# axiom_beta_plugin_module_1xHDMI_v0_2_6bb.net
KiCad netlist of a schematic drawn in EAGLE
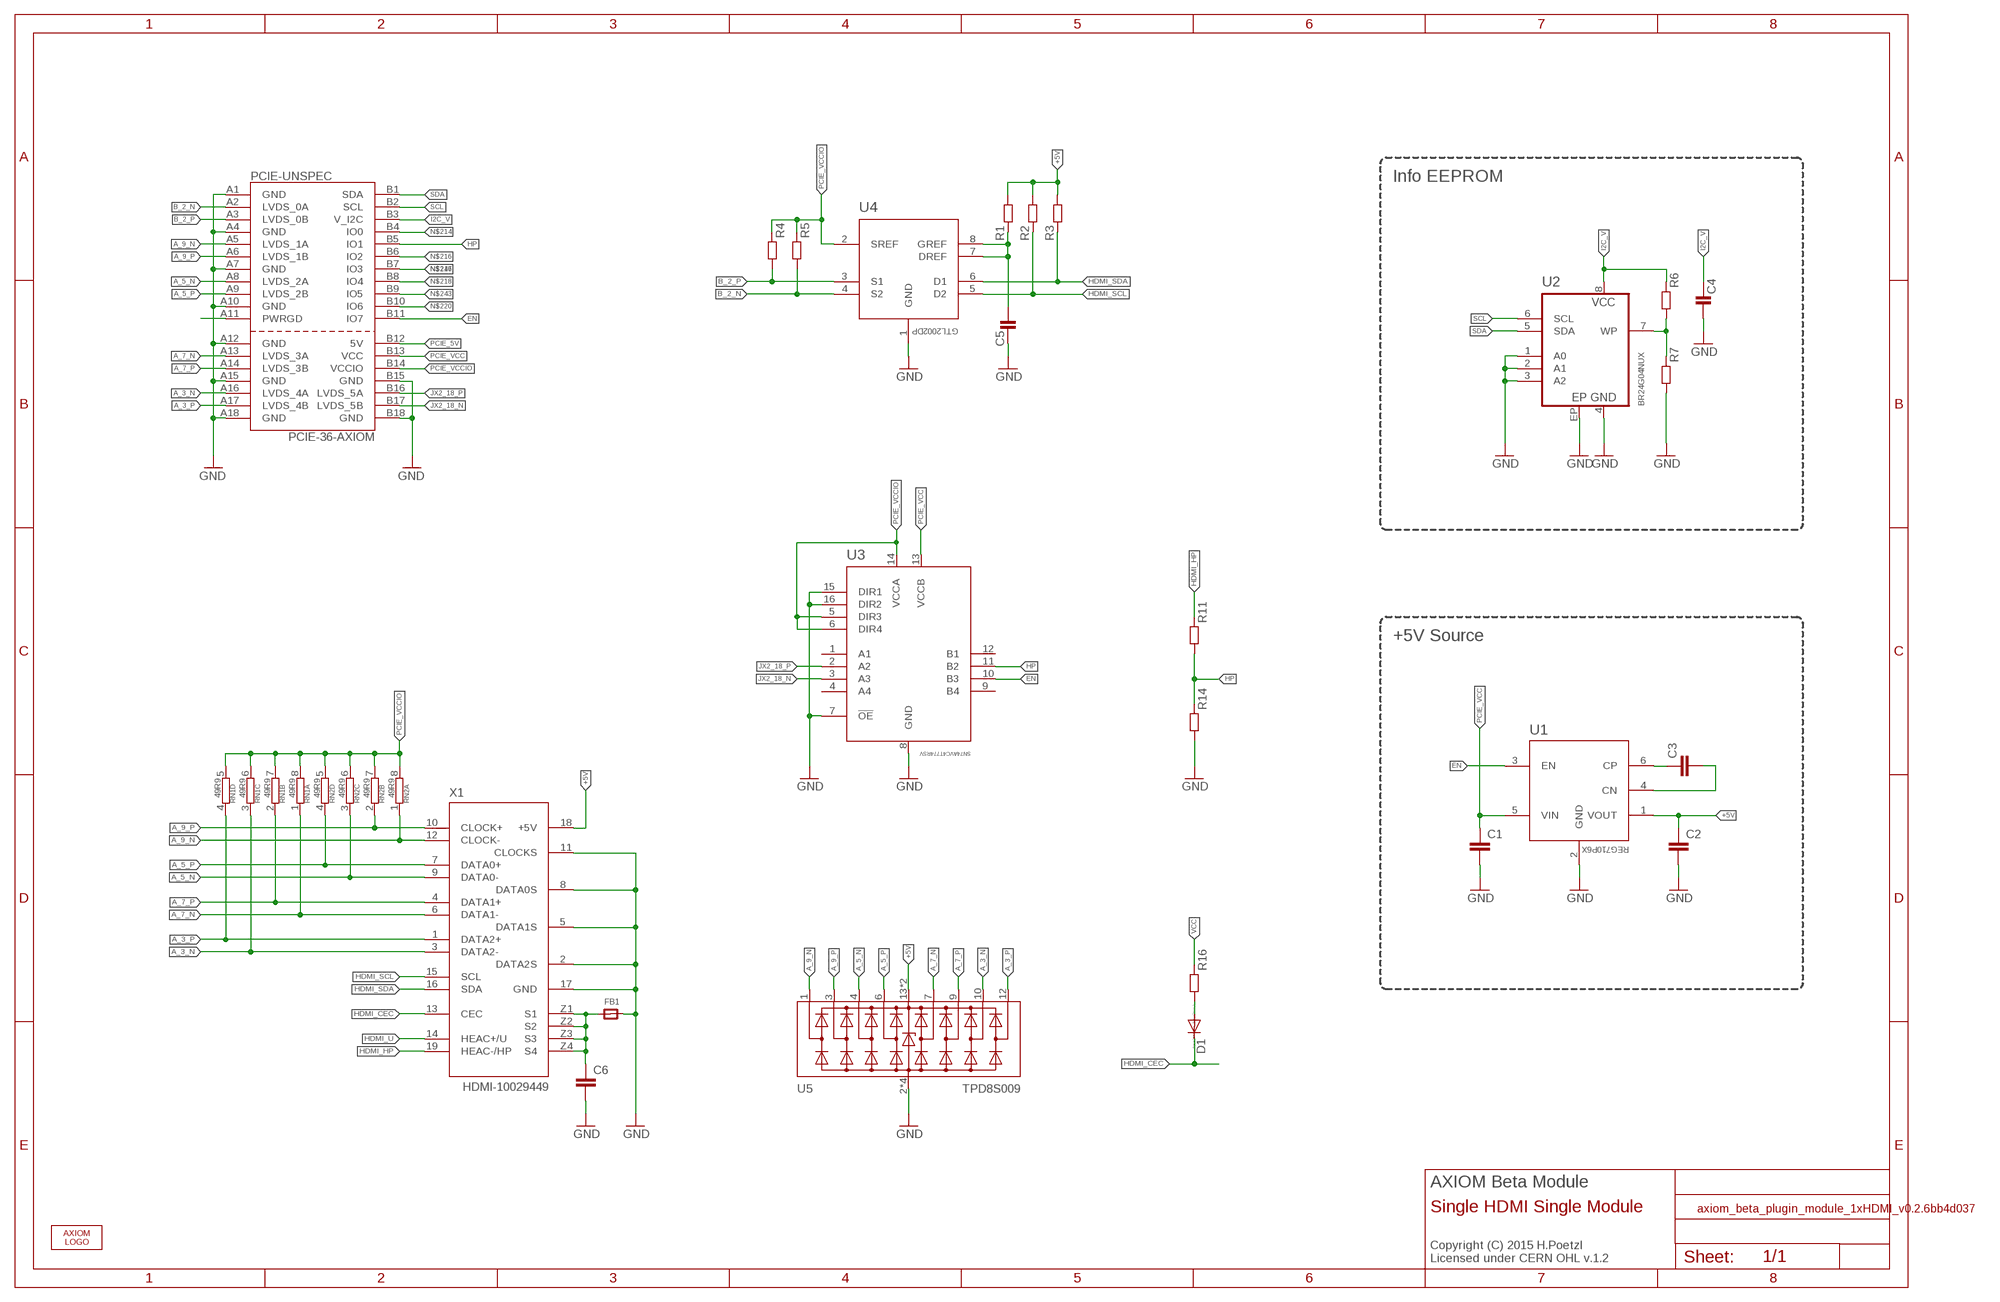
[diagram p0: schematic, sheet 1]

(export (version "E")
  (design (tool "Eeschema 10.0.6"))
  (components
    (comp (ref "C1")
      (value "C-EUC0603K")
      (footprint "eagle-import:C0603K")
      (libsource (lib "eagle-import") (part "C-EUC0603K"))
    )
    (comp (ref "C2")
      (value "C-EUC0603K")
      (footprint "eagle-import:C0603K")
      (libsource (lib "eagle-import") (part "C-EUC0603K"))
    )
    (comp (ref "C3")
      (value "C-EUC0603K")
      (footprint "eagle-import:C0603K")
      (libsource (lib "eagle-import") (part "C-EUC0603K"))
    )
    (comp (ref "C4")
      (value "C0402-B")
      (footprint "eagle-import:0402-B")
      (libsource (lib "eagle-import") (part "C0402-B"))
    )
    (comp (ref "C5")
      (value "C0402-B")
      (footprint "eagle-import:0402-B")
      (libsource (lib "eagle-import") (part "C0402-B"))
    )
    (comp (ref "C6")
      (value "C-EUC0603K")
      (footprint "eagle-import:C0603K")
      (libsource (lib "eagle-import") (part "C-EUC0603K"))
    )
    (comp (ref "D1")
      (value "DIODE-SOD523")
      (footprint "eagle-import:SOD523")
      (libsource (lib "eagle-import") (part "DIODE-SOD523"))
    )
    (comp (ref "FB1")
      (value "FERRITE_0603MP")
      (footprint "eagle-import:_0603MP")
      (libsource (lib "eagle-import") (part "FERRITE_0603MP"))
    )
    (comp (ref "PCIE-UNSPEC")
      (value "PCIE-36-AXIOM")
      (footprint "eagle-import:PCIE-36-AXIOM")
      (libsource (lib "eagle-import") (part "PCIE-36-AXIOM"))
    )
    (comp (ref "R1")
      (value "R0402-B")
      (footprint "eagle-import:0402-B")
      (libsource (lib "eagle-import") (part "R0402-B"))
    )
    (comp (ref "R2")
      (value "R0402-B")
      (footprint "eagle-import:0402-B")
      (libsource (lib "eagle-import") (part "R0402-B"))
    )
    (comp (ref "R3")
      (value "R0402-B")
      (footprint "eagle-import:0402-B")
      (libsource (lib "eagle-import") (part "R0402-B"))
    )
    (comp (ref "R4")
      (value "R0402-B")
      (footprint "eagle-import:0402-B")
      (libsource (lib "eagle-import") (part "R0402-B"))
    )
    (comp (ref "R5")
      (value "R0402-B")
      (footprint "eagle-import:0402-B")
      (libsource (lib "eagle-import") (part "R0402-B"))
    )
    (comp (ref "R6")
      (value "R0402-B")
      (footprint "eagle-import:0402-B")
      (libsource (lib "eagle-import") (part "R0402-B"))
    )
    (comp (ref "R7")
      (value "R0603-B")
      (footprint "eagle-import:0603-B")
      (libsource (lib "eagle-import") (part "R0603-B"))
    )
    (comp (ref "R11")
      (value "R0402-B")
      (footprint "eagle-import:0402-B")
      (libsource (lib "eagle-import") (part "R0402-B"))
    )
    (comp (ref "R14")
      (value "R0402-B")
      (footprint "eagle-import:0402-B")
      (libsource (lib "eagle-import") (part "R0402-B"))
    )
    (comp (ref "R16")
      (value "R0402-B")
      (footprint "eagle-import:0402-B")
      (libsource (lib "eagle-import") (part "R0402-B"))
    )
    (comp (ref "RN1")
      (value "49R9")
      (footprint "eagle-import:CAY16")
      (libsource (lib "eagle-import") (part "4R-NCAY16"))
    )
    (comp (ref "RN2")
      (value "49R9")
      (footprint "eagle-import:CAY16")
      (libsource (lib "eagle-import") (part "4R-NCAY16"))
    )
    (comp (ref "U$1")
      (value "AXIOM_LOGO262X40")
      (footprint "eagle-import:AXIOM_LOGO_262X40")
      (libsource (lib "eagle-import") (part "AXIOM_LOGO262X40"))
    )
    (comp (ref "U1")
      (value "REG710P6X")
      (footprint "eagle-import:SOT65P210X110-6N")
      (libsource (lib "eagle-import") (part "REG710P6X"))
    )
    (comp (ref "U2")
      (value "BR24G04NUX")
      (footprint "eagle-import:DFN200X300X100-9N")
      (libsource (lib "eagle-import") (part "BR24G04NUX"))
    )
    (comp (ref "U3")
      (value "SN74AVC4T774RSV")
      (footprint "eagle-import:QFN40P185X265X55-16N")
      (libsource (lib "eagle-import") (part "SN74AVC4T774RSV"))
    )
    (comp (ref "U4")
      (value "GTL2002DP")
      (footprint "eagle-import:TSSOP-8")
      (libsource (lib "eagle-import") (part "GTL2002DP"))
    )
    (comp (ref "U5")
      (value "TPD8S009")
      (footprint "eagle-import:R-PDSO-N15")
      (libsource (lib "eagle-import") (part "TPD8S009"))
    )
    (comp (ref "X1")
      (value "HDMI-10029449")
      (footprint "eagle-import:10029449-X01XLF")
      (libsource (lib "eagle-import") (part "HDMI-10029449"))
    )
  )
  (nets
    (net (code "1") (name "+5V") (class "Default")
      (node (ref "C2") (pin "1") (pinfunction "1_1") (pintype "passive"))
      (node (ref "R1") (pin "2") (pinfunction "2_2") (pintype "passive"))
      (node (ref "R2") (pin "2") (pinfunction "2_2") (pintype "passive"))
      (node (ref "R3") (pin "2") (pinfunction "2_2") (pintype "passive"))
      (node (ref "U1") (pin "1") (pinfunction "VOUT_1") (pintype "output"))
      (node (ref "U5") (pin "13") (pinfunction "VCC_13") (pintype "power_in"))
      (node (ref "U5") (pin "15") (pinfunction "VCC_15") (pintype "power_in"))
      (node (ref "X1") (pin "18") (pinfunction "+5V_18") (pintype "power_in"))
    )
    (net (code "2") (name "A_3_N") (class "Default")
      (node (ref "PCIE-UNSPEC") (pin "A16") (pinfunction "LVDS_4A_A16") (pintype "passive"))
      (node (ref "RN1") (pin "3") (pinfunction "1_3") (pintype "passive"))
      (node (ref "U5") (pin "10") (pinfunction "ESD7_10") (pintype "passive"))
      (node (ref "X1") (pin "3") (pinfunction "DATA2-_3") (pintype "bidirectional"))
    )
    (net (code "3") (name "A_3_P") (class "Default")
      (node (ref "PCIE-UNSPEC") (pin "A17") (pinfunction "LVDS_4B_A17") (pintype "passive"))
      (node (ref "RN1") (pin "4") (pinfunction "1_4") (pintype "passive"))
      (node (ref "U5") (pin "12") (pinfunction "ESD8_12") (pintype "passive"))
      (node (ref "X1") (pin "1") (pinfunction "DATA2+_1") (pintype "bidirectional"))
    )
    (net (code "4") (name "A_5_N") (class "Default")
      (node (ref "PCIE-UNSPEC") (pin "A8") (pinfunction "LVDS_2A_A8") (pintype "passive"))
      (node (ref "RN2") (pin "3") (pinfunction "1_3") (pintype "passive"))
      (node (ref "U5") (pin "4") (pinfunction "ESD3_4") (pintype "passive"))
      (node (ref "X1") (pin "9") (pinfunction "DATA0-_9") (pintype "bidirectional"))
    )
    (net (code "5") (name "A_5_P") (class "Default")
      (node (ref "PCIE-UNSPEC") (pin "A9") (pinfunction "LVDS_2B_A9") (pintype "passive"))
      (node (ref "RN2") (pin "4") (pinfunction "1_4") (pintype "passive"))
      (node (ref "U5") (pin "6") (pinfunction "ESD4_6") (pintype "passive"))
      (node (ref "X1") (pin "7") (pinfunction "DATA0+_7") (pintype "bidirectional"))
    )
    (net (code "6") (name "A_7_N") (class "Default")
      (node (ref "PCIE-UNSPEC") (pin "A13") (pinfunction "LVDS_3A_A13") (pintype "passive"))
      (node (ref "RN1") (pin "1") (pinfunction "1_1") (pintype "passive"))
      (node (ref "U5") (pin "7") (pinfunction "ESD5_7") (pintype "passive"))
      (node (ref "X1") (pin "6") (pinfunction "DATA1-_6") (pintype "bidirectional"))
    )
    (net (code "7") (name "A_7_P") (class "Default")
      (node (ref "PCIE-UNSPEC") (pin "A14") (pinfunction "LVDS_3B_A14") (pintype "passive"))
      (node (ref "RN1") (pin "2") (pinfunction "1_2") (pintype "passive"))
      (node (ref "U5") (pin "9") (pinfunction "ESD6_9") (pintype "passive"))
      (node (ref "X1") (pin "4") (pinfunction "DATA1+_4") (pintype "bidirectional"))
    )
    (net (code "8") (name "A_9_N") (class "Default")
      (node (ref "PCIE-UNSPEC") (pin "A5") (pinfunction "LVDS_1A_A5") (pintype "passive"))
      (node (ref "RN2") (pin "1") (pinfunction "1_1") (pintype "passive"))
      (node (ref "U5") (pin "1") (pinfunction "ESD1_1") (pintype "passive"))
      (node (ref "X1") (pin "12") (pinfunction "CLOCK-_12") (pintype "bidirectional"))
    )
    (net (code "9") (name "A_9_P") (class "Default")
      (node (ref "PCIE-UNSPEC") (pin "A6") (pinfunction "LVDS_1B_A6") (pintype "passive"))
      (node (ref "RN2") (pin "2") (pinfunction "1_2") (pintype "passive"))
      (node (ref "U5") (pin "3") (pinfunction "ESD2_3") (pintype "passive"))
      (node (ref "X1") (pin "10") (pinfunction "CLOCK+_10") (pintype "bidirectional"))
    )
    (net (code "10") (name "B_2_N") (class "Default")
      (node (ref "PCIE-UNSPEC") (pin "A2") (pinfunction "LVDS_0A_A2") (pintype "passive"))
      (node (ref "R5") (pin "2") (pinfunction "2_2") (pintype "passive"))
      (node (ref "U4") (pin "4") (pinfunction "S2_4") (pintype "bidirectional"))
    )
    (net (code "11") (name "B_2_P") (class "Default")
      (node (ref "PCIE-UNSPEC") (pin "A3") (pinfunction "LVDS_0B_A3") (pintype "passive"))
      (node (ref "R4") (pin "2") (pinfunction "2_2") (pintype "passive"))
      (node (ref "U4") (pin "3") (pinfunction "S1_3") (pintype "bidirectional"))
    )
    (net (code "12") (name "EN") (class "Default")
      (node (ref "PCIE-UNSPEC") (pin "B11") (pinfunction "IO7_B11") (pintype "passive"))
      (node (ref "U1") (pin "3") (pinfunction "EN_3") (pintype "input"))
      (node (ref "U3") (pin "10") (pinfunction "B3_10") (pintype "bidirectional"))
    )
    (net (code "13") (name "GND") (class "Default")
      (node (ref "C1") (pin "2") (pinfunction "2_2") (pintype "passive"))
      (node (ref "C2") (pin "2") (pinfunction "2_2") (pintype "passive"))
      (node (ref "C4") (pin "2") (pinfunction "2_2") (pintype "passive"))
      (node (ref "C5") (pin "1") (pinfunction "1_1") (pintype "passive"))
      (node (ref "C6") (pin "2") (pinfunction "2_2") (pintype "passive"))
      (node (ref "FB1") (pin "2") (pinfunction "P$2_2") (pintype "passive"))
      (node (ref "PCIE-UNSPEC") (pin "A1") (pinfunction "GND_A1") (pintype "passive"))
      (node (ref "PCIE-UNSPEC") (pin "A10") (pinfunction "GND_A10") (pintype "passive"))
      (node (ref "PCIE-UNSPEC") (pin "A12") (pinfunction "GND_A12") (pintype "passive"))
      (node (ref "PCIE-UNSPEC") (pin "A15") (pinfunction "GND_A15") (pintype "passive"))
      (node (ref "PCIE-UNSPEC") (pin "A18") (pinfunction "GND_A18") (pintype "passive"))
      (node (ref "PCIE-UNSPEC") (pin "A4") (pinfunction "GND_A4") (pintype "passive"))
      (node (ref "PCIE-UNSPEC") (pin "A7") (pinfunction "GND_A7") (pintype "passive"))
      (node (ref "PCIE-UNSPEC") (pin "B15") (pinfunction "GND_B15") (pintype "passive"))
      (node (ref "PCIE-UNSPEC") (pin "B18") (pinfunction "GND_B18") (pintype "passive"))
      (node (ref "R14") (pin "2") (pinfunction "2_2") (pintype "passive"))
      (node (ref "R7") (pin "2") (pinfunction "2_2") (pintype "passive"))
      (node (ref "U1") (pin "2") (pinfunction "GND_2") (pintype "passive"))
      (node (ref "U2") (pin "1") (pinfunction "A0_1") (pintype "input"))
      (node (ref "U2") (pin "2") (pinfunction "A1_2") (pintype "input"))
      (node (ref "U2") (pin "3") (pinfunction "A2_3") (pintype "input"))
      (node (ref "U2") (pin "4") (pinfunction "GND_4") (pintype "passive"))
      (node (ref "U2") (pin "EP") (pinfunction "EP_EP") (pintype "passive"))
      (node (ref "U3") (pin "15") (pinfunction "DIR1_15") (pintype "input"))
      (node (ref "U3") (pin "16") (pinfunction "DIR2_16") (pintype "input"))
      (node (ref "U3") (pin "7") (pinfunction "~{OE}_7") (pintype "input"))
      (node (ref "U3") (pin "8") (pinfunction "GND_8") (pintype "passive"))
      (node (ref "U4") (pin "1") (pinfunction "GND_1") (pintype "passive"))
      (node (ref "U5") (pin "11") (pinfunction "GND_11") (pintype "power_in"))
      (node (ref "U5") (pin "2") (pinfunction "GND_2") (pintype "power_in"))
      (node (ref "U5") (pin "5") (pinfunction "GND_5") (pintype "power_in"))
      (node (ref "U5") (pin "8") (pinfunction "GND_8") (pintype "power_in"))
      (node (ref "X1") (pin "11") (pinfunction "CLOCKS_11") (pintype "power_in"))
      (node (ref "X1") (pin "17") (pinfunction "GND_17") (pintype "bidirectional"))
      (node (ref "X1") (pin "2") (pinfunction "DATA2S_2") (pintype "power_in"))
      (node (ref "X1") (pin "5") (pinfunction "DATA1S_5") (pintype "power_in"))
      (node (ref "X1") (pin "8") (pinfunction "DATA0S_8") (pintype "power_in"))
    )
    (net (code "14") (name "HDMI_CEC") (class "Default")
      (node (ref "D1") (pin "C") (pinfunction "C_C") (pintype "passive"))
      (node (ref "X1") (pin "13") (pinfunction "CEC_13") (pintype "bidirectional"))
    )
    (net (code "15") (name "HDMI_HP") (class "Default")
      (node (ref "R11") (pin "1") (pinfunction "1_1") (pintype "passive"))
      (node (ref "X1") (pin "19") (pinfunction "HEAC-/HP_19") (pintype "bidirectional"))
    )
    (net (code "16") (name "HDMI_SCL") (class "Default")
      (node (ref "R2") (pin "1") (pinfunction "1_1") (pintype "passive"))
      (node (ref "U4") (pin "5") (pinfunction "D2_5") (pintype "bidirectional"))
      (node (ref "X1") (pin "15") (pinfunction "SCL_15") (pintype "bidirectional"))
    )
    (net (code "17") (name "HDMI_SDA") (class "Default")
      (node (ref "R3") (pin "1") (pinfunction "1_1") (pintype "passive"))
      (node (ref "U4") (pin "6") (pinfunction "D1_6") (pintype "bidirectional"))
      (node (ref "X1") (pin "16") (pinfunction "SDA_16") (pintype "bidirectional"))
    )
    (net (code "18") (name "HDMI_U") (class "Default")
      (node (ref "X1") (pin "14") (pinfunction "HEAC+/U_14") (pintype "bidirectional"))
    )
    (net (code "19") (name "HP") (class "Default")
      (node (ref "PCIE-UNSPEC") (pin "B5") (pinfunction "IO1_B5") (pintype "passive"))
      (node (ref "R11") (pin "2") (pinfunction "2_2") (pintype "passive"))
      (node (ref "R14") (pin "1") (pinfunction "1_1") (pintype "passive"))
      (node (ref "U3") (pin "11") (pinfunction "B2_11") (pintype "bidirectional"))
    )
    (net (code "20") (name "I2C_V") (class "Default")
      (node (ref "C4") (pin "1") (pinfunction "1_1") (pintype "passive"))
      (node (ref "PCIE-UNSPEC") (pin "B3") (pinfunction "V_I2C_B3") (pintype "passive"))
      (node (ref "R6") (pin "1") (pinfunction "1_1") (pintype "passive"))
      (node (ref "U2") (pin "8") (pinfunction "VCC_8") (pintype "power_in"))
    )
    (net (code "21") (name "JX2_18_N") (class "Default")
      (node (ref "PCIE-UNSPEC") (pin "B17") (pinfunction "LVDS_5B_B17") (pintype "passive"))
      (node (ref "U3") (pin "3") (pinfunction "A3_3") (pintype "bidirectional"))
    )
    (net (code "22") (name "JX2_18_P") (class "Default")
      (node (ref "PCIE-UNSPEC") (pin "B16") (pinfunction "LVDS_5A_B16") (pintype "passive"))
      (node (ref "U3") (pin "2") (pinfunction "A2_2") (pintype "bidirectional"))
    )
    (net (code "23") (name "N$214") (class "Default")
      (node (ref "PCIE-UNSPEC") (pin "B4") (pinfunction "IO0_B4") (pintype "passive"))
    )
    (net (code "24") (name "N$216") (class "Default")
      (node (ref "PCIE-UNSPEC") (pin "B6") (pinfunction "IO2_B6") (pintype "passive"))
    )
    (net (code "25") (name "N$218") (class "Default")
      (node (ref "PCIE-UNSPEC") (pin "B8") (pinfunction "IO4_B8") (pintype "passive"))
    )
    (net (code "26") (name "N$220") (class "Default")
      (node (ref "PCIE-UNSPEC") (pin "B10") (pinfunction "IO6_B10") (pintype "passive"))
    )
    (net (code "27") (name "N$243") (class "Default")
      (node (ref "PCIE-UNSPEC") (pin "B9") (pinfunction "IO5_B9") (pintype "passive"))
    )
    (net (code "28") (name "N$247") (class "Default")
      (node (ref "PCIE-UNSPEC") (pin "B7") (pinfunction "IO3_B7") (pintype "passive"))
    )
    (net (code "29") (name "Net-(D1-PadA)") (class "Default")
      (node (ref "D1") (pin "A") (pinfunction "A_A") (pintype "passive"))
      (node (ref "R16") (pin "2") (pinfunction "2_2") (pintype "passive"))
    )
    (net (code "30") (name "Net-(FB1-P$1)") (class "Default")
      (node (ref "C6") (pin "1") (pinfunction "1_1") (pintype "passive"))
      (node (ref "FB1") (pin "1") (pinfunction "P$1_1") (pintype "passive"))
      (node (ref "X1") (pin "Z1") (pinfunction "S1_Z1") (pintype "power_in"))
      (node (ref "X1") (pin "Z2") (pinfunction "S2_Z2") (pintype "power_in"))
      (node (ref "X1") (pin "Z3") (pinfunction "S3_Z3") (pintype "power_in"))
      (node (ref "X1") (pin "Z4") (pinfunction "S4_Z4") (pintype "power_in"))
    )
    (net (code "31") (name "Net-(U1-CN)") (class "Default")
      (node (ref "C3") (pin "2") (pinfunction "2_2") (pintype "passive"))
      (node (ref "U1") (pin "4") (pinfunction "CN_4") (pintype "power_in"))
    )
    (net (code "32") (name "Net-(U1-CP)") (class "Default")
      (node (ref "C3") (pin "1") (pinfunction "1_1") (pintype "passive"))
      (node (ref "U1") (pin "6") (pinfunction "CP_6") (pintype "output"))
    )
    (net (code "33") (name "Net-(U2-WP)") (class "Default")
      (node (ref "R6") (pin "2") (pinfunction "2_2") (pintype "passive"))
      (node (ref "R7") (pin "1") (pinfunction "1_1") (pintype "passive"))
      (node (ref "U2") (pin "7") (pinfunction "WP_7") (pintype "input"))
    )
    (net (code "34") (name "Net-(U4-DREF)") (class "Default")
      (node (ref "C5") (pin "2") (pinfunction "2_2") (pintype "passive"))
      (node (ref "R1") (pin "1") (pinfunction "1_1") (pintype "passive"))
      (node (ref "U4") (pin "7") (pinfunction "DREF_7") (pintype "passive"))
      (node (ref "U4") (pin "8") (pinfunction "GREF_8") (pintype "passive"))
    )
    (net (code "35") (name "PCIE_5V") (class "Default")
      (node (ref "PCIE-UNSPEC") (pin "B12") (pinfunction "5V_B12") (pintype "passive"))
    )
    (net (code "36") (name "PCIE_VCC") (class "Default")
      (node (ref "C1") (pin "1") (pinfunction "1_1") (pintype "passive"))
      (node (ref "PCIE-UNSPEC") (pin "B13") (pinfunction "VCC_B13") (pintype "passive"))
      (node (ref "U1") (pin "5") (pinfunction "VIN_5") (pintype "power_in"))
      (node (ref "U3") (pin "13") (pinfunction "VCCB_13") (pintype "power_in"))
    )
    (net (code "37") (name "PCIE_VCCIO") (class "Default")
      (node (ref "PCIE-UNSPEC") (pin "B14") (pinfunction "VCCIO_B14") (pintype "passive"))
      (node (ref "R4") (pin "1") (pinfunction "1_1") (pintype "passive"))
      (node (ref "R5") (pin "1") (pinfunction "1_1") (pintype "passive"))
      (node (ref "RN1") (pin "5") (pinfunction "2_5") (pintype "passive"))
      (node (ref "RN1") (pin "6") (pinfunction "2_6") (pintype "passive"))
      (node (ref "RN1") (pin "7") (pinfunction "2_7") (pintype "passive"))
      (node (ref "RN1") (pin "8") (pinfunction "2_8") (pintype "passive"))
      (node (ref "RN2") (pin "5") (pinfunction "2_5") (pintype "passive"))
      (node (ref "RN2") (pin "6") (pinfunction "2_6") (pintype "passive"))
      (node (ref "RN2") (pin "7") (pinfunction "2_7") (pintype "passive"))
      (node (ref "RN2") (pin "8") (pinfunction "2_8") (pintype "passive"))
      (node (ref "U3") (pin "14") (pinfunction "VCCA_14") (pintype "power_in"))
      (node (ref "U3") (pin "5") (pinfunction "DIR3_5") (pintype "input"))
      (node (ref "U3") (pin "6") (pinfunction "DIR4_6") (pintype "input"))
      (node (ref "U4") (pin "2") (pinfunction "SREF_2") (pintype "passive"))
    )
    (net (code "38") (name "SCL") (class "Default")
      (node (ref "PCIE-UNSPEC") (pin "B2") (pinfunction "SCL_B2") (pintype "passive"))
      (node (ref "U2") (pin "6") (pinfunction "SCL_6") (pintype "input"))
    )
    (net (code "39") (name "SDA") (class "Default")
      (node (ref "PCIE-UNSPEC") (pin "B1") (pinfunction "SDA_B1") (pintype "passive"))
      (node (ref "U2") (pin "5") (pinfunction "SDA_5") (pintype "bidirectional"))
    )
    (net (code "40") (name "VCC") (class "Default")
      (node (ref "R16") (pin "1") (pinfunction "1_1") (pintype "passive"))
    )
    (net (code "41") (name "unconnected-(PCIE-UNSPEC-PWRGD-PadA11)") (class "Default")
      (node (ref "PCIE-UNSPEC") (pin "A11") (pinfunction "PWRGD_A11") (pintype "passive"))
    )
    (net (code "42") (name "unconnected-(U3-A1-Pad1)") (class "Default")
      (node (ref "U3") (pin "1") (pinfunction "A1_1") (pintype "bidirectional"))
    )
    (net (code "43") (name "unconnected-(U3-A4-Pad4)") (class "Default")
      (node (ref "U3") (pin "4") (pinfunction "A4_4") (pintype "bidirectional"))
    )
    (net (code "44") (name "unconnected-(U3-B1-Pad12)") (class "Default")
      (node (ref "U3") (pin "12") (pinfunction "B1_12") (pintype "bidirectional"))
    )
    (net (code "45") (name "unconnected-(U3-B4-Pad9)") (class "Default")
      (node (ref "U3") (pin "9") (pinfunction "B4_9") (pintype "bidirectional"))
    )
  )
)
